# XMEGAbreakoutSMD.net
KiCad netlist of a schematic drawn in EAGLE
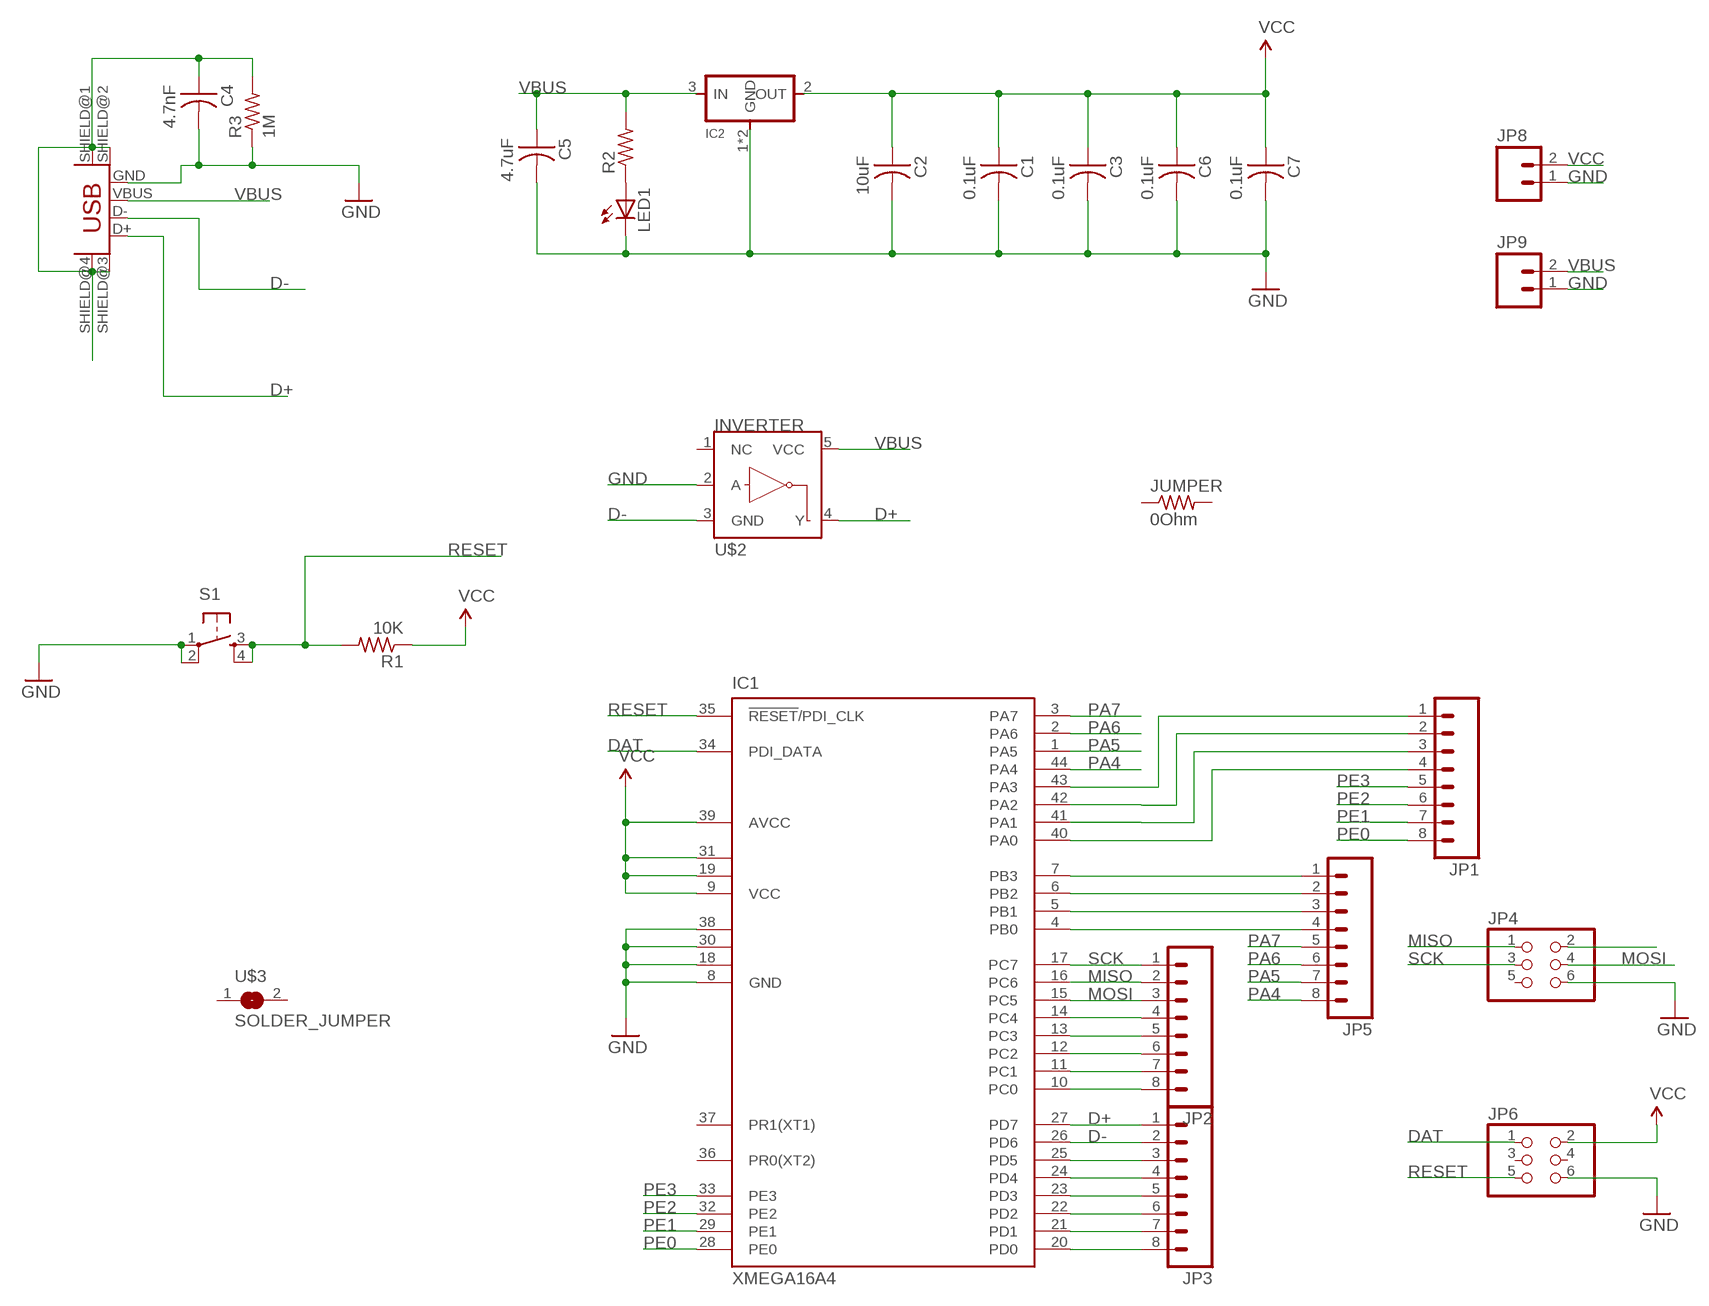
[diagram p0: schematic, sheet 1]

(export (version "E")
  (design (tool "Eeschema 10.0.6"))
  (components
    (comp (ref "C1")
      (value "0.1uF")
      (footprint "eagle-import:C1206")
      (libsource (lib "eagle-import") (part "CAP-US1206"))
    )
    (comp (ref "C2")
      (value "10uF")
      (footprint "eagle-import:C1206")
      (libsource (lib "eagle-import") (part "CAP-US1206"))
    )
    (comp (ref "C3")
      (value "0.1uF")
      (footprint "eagle-import:C1206FAB")
      (libsource (lib "eagle-import") (part "CAP-US1206FAB"))
    )
    (comp (ref "C4")
      (value "4.7nF")
      (footprint "eagle-import:C1206")
      (libsource (lib "eagle-import") (part "CAP-US1206"))
    )
    (comp (ref "C5")
      (value "4.7uF")
      (footprint "eagle-import:C1206")
      (libsource (lib "eagle-import") (part "CAP-US1206"))
    )
    (comp (ref "C6")
      (value "0.1uF")
      (footprint "eagle-import:C1206")
      (libsource (lib "eagle-import") (part "CAP-US1206"))
    )
    (comp (ref "C7")
      (value "0.1uF")
      (footprint "eagle-import:C1206")
      (libsource (lib "eagle-import") (part "CAP-US1206"))
    )
    (comp (ref "IC1")
      (value "XMEGA16A4")
      (footprint "eagle-import:TQFP44-FAB")
      (libsource (lib "eagle-import") (part "XMEGA16A4"))
    )
    (comp (ref "IC2")
      (value "REGULATORSOT223")
      (footprint "eagle-import:SOT223")
      (libsource (lib "eagle-import") (part "REGULATORSOT223"))
    )
    (comp (ref "JP1")
      (value "M08")
      (footprint "eagle-import:1X08_SMD_ALT_2X1X4")
      (libsource (lib "eagle-import") (part "M08"))
    )
    (comp (ref "JP2")
      (value "M08SMD-STRAIGHT-ALT")
      (footprint "eagle-import:1X08_SMD_ALT")
      (libsource (lib "eagle-import") (part "M08SMD-STRAIGHT-ALT"))
    )
    (comp (ref "JP3")
      (value "M08SMD-STRAIGHT-ALT")
      (footprint "eagle-import:1X08_SMD_ALT")
      (libsource (lib "eagle-import") (part "M08SMD-STRAIGHT-ALT"))
    )
    (comp (ref "JP4")
      (value "PINHD-2X3-SMD")
      (footprint "eagle-import:2X03SMD")
      (libsource (lib "eagle-import") (part "PINHD-2X3-SMD"))
    )
    (comp (ref "JP5")
      (value "M08SMD-STRAIGHT-ALT")
      (footprint "eagle-import:1X08_SMD_ALT")
      (libsource (lib "eagle-import") (part "M08SMD-STRAIGHT-ALT"))
    )
    (comp (ref "JP6")
      (value "PINHD-2X3-SMD")
      (footprint "eagle-import:2X03SMD")
      (libsource (lib "eagle-import") (part "PINHD-2X3-SMD"))
    )
    (comp (ref "JP8")
      (value "M02")
      (footprint "eagle-import:1X02_SMD_STRAIGHT_ALT")
      (libsource (lib "eagle-import") (part "M02"))
    )
    (comp (ref "JP9")
      (value "M02")
      (footprint "eagle-import:1X02_SMD_STRAIGHT_ALT")
      (libsource (lib "eagle-import") (part "M02"))
    )
    (comp (ref "JUMPER")
      (value "0Ohm")
      (footprint "eagle-import:R1206FAB")
      (libsource (lib "eagle-import") (part "RES-US1206FAB"))
    )
    (comp (ref "LED1")
      (value "LEDSMT1206")
      (footprint "eagle-import:1206")
      (libsource (lib "eagle-import") (part "LEDSMT1206"))
    )
    (comp (ref "R1")
      (value "10K")
      (footprint "eagle-import:R1206FAB")
      (libsource (lib "eagle-import") (part "RES-US1206FAB"))
    )
    (comp (ref "R2")
      (value "RES-US1206FAB")
      (footprint "eagle-import:R1206FAB")
      (libsource (lib "eagle-import") (part "RES-US1206FAB"))
    )
    (comp (ref "R3")
      (value "1M")
      (footprint "eagle-import:R1206FAB")
      (libsource (lib "eagle-import") (part "RES-US1206FAB"))
    )
    (comp (ref "S1")
      (value "6MM_SWITCH6MM_SWITCH")
      (footprint "eagle-import:6MM_SWITCH")
      (libsource (lib "eagle-import") (part "6MM_SWITCH6MM_SWITCH"))
    )
    (comp (ref "U$1")
      (value "USB_MINIB")
      (footprint "eagle-import:USB_MINIB")
      (libsource (lib "eagle-import") (part "USB_MINIB"))
    )
    (comp (ref "U$2")
      (value "INVERTER")
      (footprint "eagle-import:SOT23-5")
      (libsource (lib "eagle-import") (part "INVERTER"))
    )
    (comp (ref "U$3")
      (value "SOLDER_JUMPER")
      (footprint "eagle-import:SJFAB")
      (libsource (lib "eagle-import") (part "SOLDER_JUMPER"))
    )
  )
  (nets
    (net (code "1") (name "/D+") (class "Default")
      (node (ref "IC1") (pin "27") (pinfunction "PD7_27") (pintype "bidirectional"))
      (node (ref "JP3") (pin "1") (pinfunction "1_1") (pintype "passive"))
      (node (ref "U$1") (pin "D+") (pinfunction "D+_D+") (pintype "bidirectional"))
      (node (ref "U$2") (pin "4") (pinfunction "Y_4") (pintype "bidirectional"))
    )
    (net (code "2") (name "/D-") (class "Default")
      (node (ref "IC1") (pin "26") (pinfunction "PD6_26") (pintype "bidirectional"))
      (node (ref "JP3") (pin "2") (pinfunction "2_2") (pintype "passive"))
      (node (ref "U$1") (pin "D-") (pinfunction "D-_D-") (pintype "bidirectional"))
      (node (ref "U$2") (pin "3") (pinfunction "GND_3") (pintype "bidirectional"))
    )
    (net (code "3") (name "/DAT") (class "Default")
      (node (ref "IC1") (pin "34") (pinfunction "PDI_DATA_34") (pintype "bidirectional"))
      (node (ref "JP6") (pin "1") (pinfunction "1_1") (pintype "passive"))
    )
    (net (code "4") (name "/MISO") (class "Default")
      (node (ref "IC1") (pin "16") (pinfunction "PC6_16") (pintype "bidirectional"))
      (node (ref "JP2") (pin "2") (pinfunction "2_2") (pintype "passive"))
      (node (ref "JP4") (pin "1") (pinfunction "1_1") (pintype "passive"))
    )
    (net (code "5") (name "/MOSI") (class "Default")
      (node (ref "IC1") (pin "15") (pinfunction "PC5_15") (pintype "bidirectional"))
      (node (ref "JP2") (pin "3") (pinfunction "3_3") (pintype "passive"))
      (node (ref "JP4") (pin "4") (pinfunction "4_4") (pintype "passive"))
    )
    (net (code "6") (name "/PA4") (class "Default")
      (node (ref "IC1") (pin "44") (pinfunction "PA4_44") (pintype "bidirectional"))
      (node (ref "JP5") (pin "8") (pinfunction "8_8") (pintype "passive"))
    )
    (net (code "7") (name "/PA5") (class "Default")
      (node (ref "IC1") (pin "1") (pinfunction "PA5_1") (pintype "bidirectional"))
      (node (ref "JP5") (pin "7") (pinfunction "7_7") (pintype "passive"))
    )
    (net (code "8") (name "/PA6") (class "Default")
      (node (ref "IC1") (pin "2") (pinfunction "PA6_2") (pintype "bidirectional"))
      (node (ref "JP5") (pin "6") (pinfunction "6_6") (pintype "passive"))
    )
    (net (code "9") (name "/PA7") (class "Default")
      (node (ref "IC1") (pin "3") (pinfunction "PA7_3") (pintype "bidirectional"))
      (node (ref "JP5") (pin "5") (pinfunction "5_5") (pintype "passive"))
    )
    (net (code "10") (name "/PE0") (class "Default")
      (node (ref "IC1") (pin "28") (pinfunction "PE0_28") (pintype "bidirectional"))
      (node (ref "JP1") (pin "8") (pinfunction "8_8") (pintype "passive"))
    )
    (net (code "11") (name "/PE1") (class "Default")
      (node (ref "IC1") (pin "29") (pinfunction "PE1_29") (pintype "bidirectional"))
      (node (ref "JP1") (pin "7") (pinfunction "7_7") (pintype "passive"))
    )
    (net (code "12") (name "/PE2") (class "Default")
      (node (ref "IC1") (pin "32") (pinfunction "PE2_32") (pintype "bidirectional"))
      (node (ref "JP1") (pin "6") (pinfunction "6_6") (pintype "passive"))
    )
    (net (code "13") (name "/PE3") (class "Default")
      (node (ref "IC1") (pin "33") (pinfunction "PE3_33") (pintype "bidirectional"))
      (node (ref "JP1") (pin "5") (pinfunction "5_5") (pintype "passive"))
    )
    (net (code "14") (name "/RESET") (class "Default")
      (node (ref "IC1") (pin "35") (pinfunction "~{RESET}/PDI_CLK_35") (pintype "bidirectional"))
      (node (ref "JP6") (pin "5") (pinfunction "5_5") (pintype "passive"))
      (node (ref "R1") (pin "2") (pinfunction "2_2") (pintype "passive"))
      (node (ref "S1") (pin "3") (pinfunction "S_3") (pintype "passive"))
      (node (ref "S1") (pin "4") (pinfunction "S1_4") (pintype "passive"))
    )
    (net (code "15") (name "/SCK") (class "Default")
      (node (ref "IC1") (pin "17") (pinfunction "PC7_17") (pintype "bidirectional"))
      (node (ref "JP2") (pin "1") (pinfunction "1_1") (pintype "passive"))
      (node (ref "JP4") (pin "3") (pinfunction "3_3") (pintype "passive"))
    )
    (net (code "16") (name "/VBUS") (class "Default")
      (node (ref "C5") (pin "1") (pinfunction "1_1") (pintype "passive"))
      (node (ref "IC2") (pin "3") (pinfunction "IN_3") (pintype "bidirectional"))
      (node (ref "JP9") (pin "2") (pinfunction "2_2") (pintype "passive"))
      (node (ref "R2") (pin "2") (pinfunction "2_2") (pintype "passive"))
      (node (ref "U$1") (pin "VBUS") (pinfunction "VBUS_VBUS") (pintype "bidirectional"))
      (node (ref "U$2") (pin "5") (pinfunction "VCC_5") (pintype "bidirectional"))
    )
    (net (code "17") (name "GND") (class "Default")
      (node (ref "C1") (pin "2") (pinfunction "2_2") (pintype "passive"))
      (node (ref "C2") (pin "2") (pinfunction "2_2") (pintype "passive"))
      (node (ref "C3") (pin "2") (pinfunction "2_2") (pintype "passive"))
      (node (ref "C4") (pin "2") (pinfunction "2_2") (pintype "passive"))
      (node (ref "C5") (pin "2") (pinfunction "2_2") (pintype "passive"))
      (node (ref "C6") (pin "2") (pinfunction "2_2") (pintype "passive"))
      (node (ref "C7") (pin "2") (pinfunction "2_2") (pintype "passive"))
      (node (ref "IC1") (pin "18") (pinfunction "GND1_18") (pintype "power_in"))
      (node (ref "IC1") (pin "30") (pinfunction "GND2_30") (pintype "power_in"))
      (node (ref "IC1") (pin "38") (pinfunction "GND3_38") (pintype "power_in"))
      (node (ref "IC1") (pin "8") (pinfunction "GND_8") (pintype "power_in"))
      (node (ref "IC2") (pin "1") (pinfunction "GND_1") (pintype "bidirectional"))
      (node (ref "IC2") (pin "4") (pinfunction "GND_4") (pintype "bidirectional"))
      (node (ref "JP4") (pin "6") (pinfunction "6_6") (pintype "passive"))
      (node (ref "JP6") (pin "6") (pinfunction "6_6") (pintype "passive"))
      (node (ref "JP8") (pin "1") (pinfunction "1_1") (pintype "passive"))
      (node (ref "JP9") (pin "1") (pinfunction "1_1") (pintype "passive"))
      (node (ref "LED1") (pin "C") (pinfunction "C_C") (pintype "passive"))
      (node (ref "R3") (pin "1") (pinfunction "1_1") (pintype "passive"))
      (node (ref "S1") (pin "1") (pinfunction "P_1") (pintype "passive"))
      (node (ref "S1") (pin "2") (pinfunction "P1_2") (pintype "passive"))
      (node (ref "U$1") (pin "GND") (pinfunction "GND_GND") (pintype "bidirectional"))
      (node (ref "U$2") (pin "2") (pinfunction "A_2") (pintype "bidirectional"))
    )
    (net (code "18") (name "Net-(IC1-PA0)") (class "Default")
      (node (ref "IC1") (pin "40") (pinfunction "PA0_40") (pintype "bidirectional"))
      (node (ref "JP1") (pin "4") (pinfunction "4_4") (pintype "passive"))
    )
    (net (code "19") (name "Net-(IC1-PA1)") (class "Default")
      (node (ref "IC1") (pin "41") (pinfunction "PA1_41") (pintype "bidirectional"))
      (node (ref "JP1") (pin "3") (pinfunction "3_3") (pintype "passive"))
    )
    (net (code "20") (name "Net-(IC1-PA2)") (class "Default")
      (node (ref "IC1") (pin "42") (pinfunction "PA2_42") (pintype "bidirectional"))
      (node (ref "JP1") (pin "2") (pinfunction "2_2") (pintype "passive"))
    )
    (net (code "21") (name "Net-(IC1-PA3)") (class "Default")
      (node (ref "IC1") (pin "43") (pinfunction "PA3_43") (pintype "bidirectional"))
      (node (ref "JP1") (pin "1") (pinfunction "1_1") (pintype "passive"))
    )
    (net (code "22") (name "Net-(IC1-PB0)") (class "Default")
      (node (ref "IC1") (pin "4") (pinfunction "PB0_4") (pintype "bidirectional"))
      (node (ref "JP5") (pin "4") (pinfunction "4_4") (pintype "passive"))
    )
    (net (code "23") (name "Net-(IC1-PB1)") (class "Default")
      (node (ref "IC1") (pin "5") (pinfunction "PB1_5") (pintype "bidirectional"))
      (node (ref "JP5") (pin "3") (pinfunction "3_3") (pintype "passive"))
    )
    (net (code "24") (name "Net-(IC1-PB2)") (class "Default")
      (node (ref "IC1") (pin "6") (pinfunction "PB2_6") (pintype "bidirectional"))
      (node (ref "JP5") (pin "2") (pinfunction "2_2") (pintype "passive"))
    )
    (net (code "25") (name "Net-(IC1-PB3)") (class "Default")
      (node (ref "IC1") (pin "7") (pinfunction "PB3_7") (pintype "bidirectional"))
      (node (ref "JP5") (pin "1") (pinfunction "1_1") (pintype "passive"))
    )
    (net (code "26") (name "Net-(IC1-PC0)") (class "Default")
      (node (ref "IC1") (pin "10") (pinfunction "PC0_10") (pintype "bidirectional"))
      (node (ref "JP2") (pin "8") (pinfunction "8_8") (pintype "passive"))
    )
    (net (code "27") (name "Net-(IC1-PC1)") (class "Default")
      (node (ref "IC1") (pin "11") (pinfunction "PC1_11") (pintype "bidirectional"))
      (node (ref "JP2") (pin "7") (pinfunction "7_7") (pintype "passive"))
    )
    (net (code "28") (name "Net-(IC1-PC2)") (class "Default")
      (node (ref "IC1") (pin "12") (pinfunction "PC2_12") (pintype "bidirectional"))
      (node (ref "JP2") (pin "6") (pinfunction "6_6") (pintype "passive"))
    )
    (net (code "29") (name "Net-(IC1-PC3)") (class "Default")
      (node (ref "IC1") (pin "13") (pinfunction "PC3_13") (pintype "bidirectional"))
      (node (ref "JP2") (pin "5") (pinfunction "5_5") (pintype "passive"))
    )
    (net (code "30") (name "Net-(IC1-PC4)") (class "Default")
      (node (ref "IC1") (pin "14") (pinfunction "PC4_14") (pintype "bidirectional"))
      (node (ref "JP2") (pin "4") (pinfunction "4_4") (pintype "passive"))
    )
    (net (code "31") (name "Net-(IC1-PD0)") (class "Default")
      (node (ref "IC1") (pin "20") (pinfunction "PD0_20") (pintype "bidirectional"))
      (node (ref "JP3") (pin "8") (pinfunction "8_8") (pintype "passive"))
    )
    (net (code "32") (name "Net-(IC1-PD1)") (class "Default")
      (node (ref "IC1") (pin "21") (pinfunction "PD1_21") (pintype "bidirectional"))
      (node (ref "JP3") (pin "7") (pinfunction "7_7") (pintype "passive"))
    )
    (net (code "33") (name "Net-(IC1-PD2)") (class "Default")
      (node (ref "IC1") (pin "22") (pinfunction "PD2_22") (pintype "bidirectional"))
      (node (ref "JP3") (pin "6") (pinfunction "6_6") (pintype "passive"))
    )
    (net (code "34") (name "Net-(IC1-PD3)") (class "Default")
      (node (ref "IC1") (pin "23") (pinfunction "PD3_23") (pintype "bidirectional"))
      (node (ref "JP3") (pin "5") (pinfunction "5_5") (pintype "passive"))
    )
    (net (code "35") (name "Net-(IC1-PD4)") (class "Default")
      (node (ref "IC1") (pin "24") (pinfunction "PD4_24") (pintype "bidirectional"))
      (node (ref "JP3") (pin "4") (pinfunction "4_4") (pintype "passive"))
    )
    (net (code "36") (name "Net-(IC1-PD5)") (class "Default")
      (node (ref "IC1") (pin "25") (pinfunction "PD5_25") (pintype "bidirectional"))
      (node (ref "JP3") (pin "3") (pinfunction "3_3") (pintype "passive"))
    )
    (net (code "37") (name "Net-(LED1-PadA)") (class "Default")
      (node (ref "LED1") (pin "A") (pinfunction "A_A") (pintype "passive"))
      (node (ref "R2") (pin "1") (pinfunction "1_1") (pintype "passive"))
    )
    (net (code "38") (name "Net-(U$1-SHIELD)") (class "Default")
      (node (ref "C4") (pin "1") (pinfunction "1_1") (pintype "passive"))
      (node (ref "R3") (pin "2") (pinfunction "2_2") (pintype "passive"))
      (node (ref "U$1") (pin "SHIELD@1") (pinfunction "SHIELD_SHIELD@1") (pintype "passive"))
      (node (ref "U$1") (pin "SHIELD@2") (pinfunction "SHIELD1_SHIELD@2") (pintype "passive"))
      (node (ref "U$1") (pin "SHIELD@3") (pinfunction "SHIELD2_SHIELD@3") (pintype "passive"))
      (node (ref "U$1") (pin "SHIELD@4") (pinfunction "SHIELD3_SHIELD@4") (pintype "passive"))
    )
    (net (code "39") (name "VCC") (class "Default")
      (node (ref "C1") (pin "1") (pinfunction "1_1") (pintype "passive"))
      (node (ref "C2") (pin "1") (pinfunction "1_1") (pintype "passive"))
      (node (ref "C3") (pin "1") (pinfunction "1_1") (pintype "passive"))
      (node (ref "C6") (pin "1") (pinfunction "1_1") (pintype "passive"))
      (node (ref "C7") (pin "1") (pinfunction "1_1") (pintype "passive"))
      (node (ref "IC1") (pin "19") (pinfunction "VCC1_19") (pintype "power_in"))
      (node (ref "IC1") (pin "31") (pinfunction "VCC2_31") (pintype "power_in"))
      (node (ref "IC1") (pin "39") (pinfunction "AVCC_39") (pintype "power_in"))
      (node (ref "IC1") (pin "9") (pinfunction "VCC_9") (pintype "power_in"))
      (node (ref "IC2") (pin "2") (pinfunction "OUT_2") (pintype "bidirectional"))
      (node (ref "JP6") (pin "2") (pinfunction "2_2") (pintype "passive"))
      (node (ref "JP8") (pin "2") (pinfunction "2_2") (pintype "passive"))
      (node (ref "R1") (pin "1") (pinfunction "1_1") (pintype "passive"))
    )
    (net (code "40") (name "unconnected-(IC1-PR0(XT2)-Pad36)") (class "Default")
      (node (ref "IC1") (pin "36") (pinfunction "PR0(XT2)_36") (pintype "bidirectional"))
    )
    (net (code "41") (name "unconnected-(IC1-PR1(XT1)-Pad37)") (class "Default")
      (node (ref "IC1") (pin "37") (pinfunction "PR1(XT1)_37") (pintype "bidirectional"))
    )
    (net (code "42") (name "unconnected-(JP4-Pad2)") (class "Default")
      (node (ref "JP4") (pin "2") (pinfunction "2_2") (pintype "passive"))
    )
    (net (code "43") (name "unconnected-(JP4-Pad5)") (class "Default")
      (node (ref "JP4") (pin "5") (pinfunction "5_5") (pintype "passive"))
    )
    (net (code "44") (name "unconnected-(JP6-Pad3)") (class "Default")
      (node (ref "JP6") (pin "3") (pinfunction "3_3") (pintype "passive"))
    )
    (net (code "45") (name "unconnected-(JP6-Pad4)") (class "Default")
      (node (ref "JP6") (pin "4") (pinfunction "4_4") (pintype "passive"))
    )
    (net (code "46") (name "unconnected-(JUMPER-Pad1)") (class "Default")
      (node (ref "JUMPER") (pin "1") (pinfunction "1_1") (pintype "passive"))
    )
    (net (code "47") (name "unconnected-(JUMPER-Pad2)") (class "Default")
      (node (ref "JUMPER") (pin "2") (pinfunction "2_2") (pintype "passive"))
    )
    (net (code "48") (name "unconnected-(U$2-NC-Pad1)") (class "Default")
      (node (ref "U$2") (pin "1") (pinfunction "NC_1") (pintype "bidirectional"))
    )
    (net (code "49") (name "unconnected-(U$3-Pad1)") (class "Default")
      (node (ref "U$3") (pin "1") (pinfunction "1_1") (pintype "passive"))
    )
    (net (code "50") (name "unconnected-(U$3-Pad2)") (class "Default")
      (node (ref "U$3") (pin "2") (pinfunction "2_2") (pintype "passive"))
    )
  )
)
